# Clock_circuit.net
KiCad netlist of a schematic drawn in Altium Designer
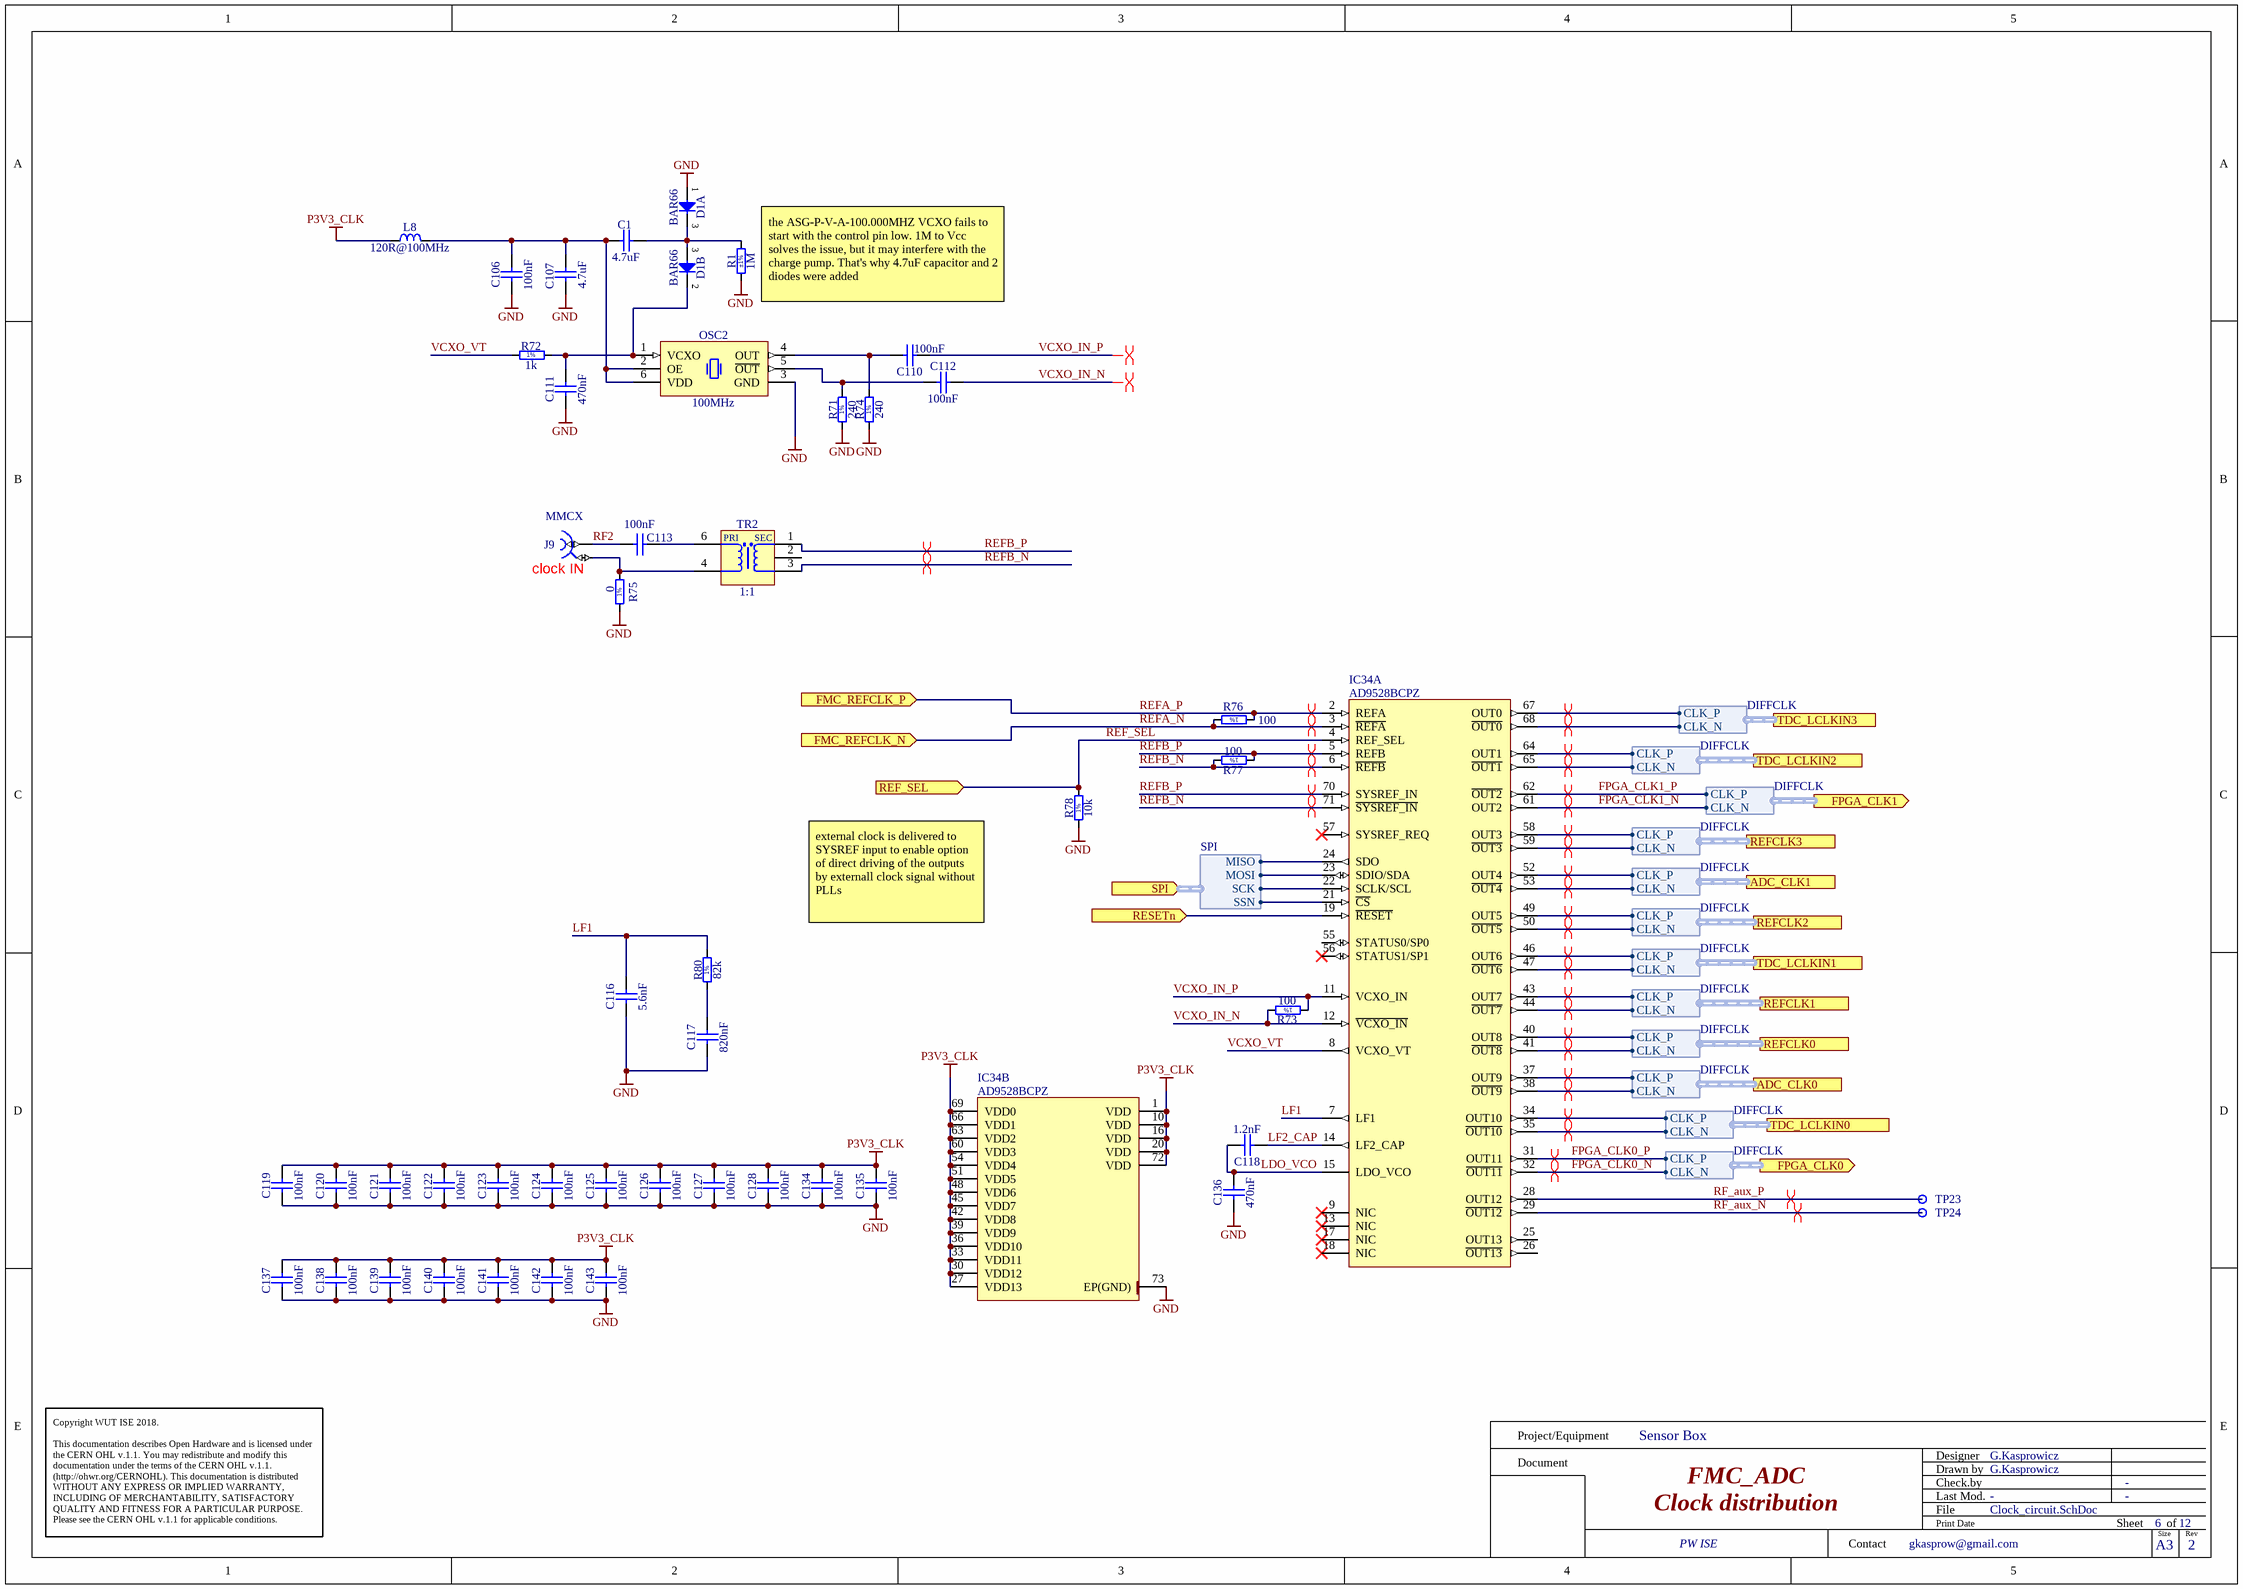
[diagram p0: Clock_circuit.SchDoc]

(export (version "E")
  (design (tool "Eeschema 10.0.6"))
  (components
    (comp (ref "C1")
      (value "4.7uF")
      (footprint "CAPC1608X87N")
      (description "Non-polarised capacitor")
      (fields
        (field (name "PART NUMBER") "CC0603_4.7UF_6.3V_10%_X5R")
        (field (name "VOLTAGE") "6.3V")
        (field (name "AUTHOR") "CERN DEM JLC")
      )
      (libsource (lib "Capacitors") (part "Capacitor - non polarized"))
    )
    (comp (ref "C106")
      (value "100nF")
      (footprint "CAPC0603X33N")
      (description "Non-polarised capacitor")
      (fields
        (field (name "TOLERANCE") "±10%")
        (field (name "PART NUMBER") "CC0201_100NF_6.3V_10%_X5R")
        (field (name "AUTHOR") "CERN DEM JLC")
      )
      (libsource (lib "Capacitors") (part "Capacitor - non polarized"))
    )
    (comp (ref "C107")
      (value "4.7uF")
      (footprint "CAPC1608X87N")
      (description "Non-polarised capacitor")
      (fields
        (field (name "PART NUMBER") "CC0603_4.7UF_6.3V_10%_X5R")
        (field (name "VOLTAGE") "6.3V")
        (field (name "AUTHOR") "CERN DEM JLC")
      )
      (libsource (lib "Capacitors") (part "Capacitor - non polarized"))
    )
    (comp (ref "C110")
      (value "100nF")
      (footprint "CAPC0603X33N")
      (description "Non-polarised capacitor")
      (fields
        (field (name "TOLERANCE") "±10%")
        (field (name "PART NUMBER") "CC0201_100NF_6.3V_10%_X5R")
        (field (name "AUTHOR") "CERN DEM JLC")
      )
      (libsource (lib "Capacitors") (part "Capacitor - non polarized"))
    )
    (comp (ref "C111")
      (value "470nF")
      (footprint "CAPC1005X55N")
      (description "Non-polarised capacitor")
      (fields
        (field (name "TOLERANCE") "±10%")
        (field (name "PART NUMBER") "CC0402_470NF_6.3V_10%_X5R")
        (field (name "AUTHOR") "CERN DEM JLC")
      )
      (libsource (lib "Capacitors") (part "Capacitor - non polarized"))
    )
    (comp (ref "C112")
      (value "100nF")
      (footprint "CAPC0603X33N")
      (description "Non-polarised capacitor")
      (fields
        (field (name "TOLERANCE") "±10%")
        (field (name "PART NUMBER") "CC0201_100NF_6.3V_10%_X5R")
        (field (name "AUTHOR") "CERN DEM JLC")
      )
      (libsource (lib "Capacitors") (part "Capacitor - non polarized"))
    )
    (comp (ref "C113")
      (value "100nF")
      (footprint "CAPC0603X33N")
      (description "Non-polarised capacitor")
      (fields
        (field (name "PART NUMBER") "CC0201_100NF_6.3V_10%_X5R")
        (field (name "VOLTAGE") "6.3V")
        (field (name "AUTHOR") "CERN DEM JLC")
      )
      (libsource (lib "Capacitors") (part "Capacitor - non polarized"))
    )
    (comp (ref "C116")
      (value "5.6nF")
      (footprint "CAPC2012X88N")
      (description "Non-polarised capacitor")
      (fields
        (field (name "PART NUMBER") "CC0805_5.6NF_50V_5%_C0G")
        (field (name "VOLTAGE") "50V")
        (field (name "AUTHOR") "*")
      )
      (libsource (lib "FMC_ADC") (part "CC0805_5.6NF_50V_5%_C0G"))
    )
    (comp (ref "C117")
      (value "820nF")
      (footprint "CAPC3216X130N")
      (description "Non-polarised capacitor")
      (fields (field (name "PART NUMBER") "CC1206_820NF_25V_10%_X7R") (field (name "VOLTAGE") "25V"))
      (libsource (lib "FMC_ADC") (part "CC1206_820NF_25V_10%_X7R"))
    )
    (comp (ref "C118")
      (value "1.2nF")
      (footprint "CAPC1608X80N")
      (description "Non-polarised capacitor")
      (fields
        (field (name "TOLERANCE") "±5%")
        (field (name "PART NUMBER") "CC0603_1.2NF_50V_5%_C0G")
        (field (name "AUTHOR") "*")
      )
      (libsource (lib "FMC_ADC") (part "CC0603_1.2NF_50V_5%_C0G"))
    )
    (comp (ref "C119")
      (value "100nF")
      (footprint "CAPC0603X33N")
      (description "Non-polarised capacitor")
      (fields
        (field (name "TOLERANCE") "±10%")
        (field (name "PART NUMBER") "CC0201_100NF_6.3V_10%_X5R")
        (field (name "AUTHOR") "CERN DEM JLC")
      )
      (libsource (lib "Capacitors") (part "Capacitor - non polarized"))
    )
    (comp (ref "C120")
      (value "100nF")
      (footprint "CAPC0603X33N")
      (description "Non-polarised capacitor")
      (fields
        (field (name "TOLERANCE") "±10%")
        (field (name "PART NUMBER") "CC0201_100NF_6.3V_10%_X5R")
        (field (name "AUTHOR") "CERN DEM JLC")
      )
      (libsource (lib "Capacitors") (part "Capacitor - non polarized"))
    )
    (comp (ref "C121")
      (value "100nF")
      (footprint "CAPC0603X33N")
      (description "Non-polarised capacitor")
      (fields
        (field (name "TOLERANCE") "±10%")
        (field (name "PART NUMBER") "CC0201_100NF_6.3V_10%_X5R")
        (field (name "AUTHOR") "CERN DEM JLC")
      )
      (libsource (lib "Capacitors") (part "Capacitor - non polarized"))
    )
    (comp (ref "C122")
      (value "100nF")
      (footprint "CAPC0603X33N")
      (description "Non-polarised capacitor")
      (fields
        (field (name "TOLERANCE") "±10%")
        (field (name "PART NUMBER") "CC0201_100NF_6.3V_10%_X5R")
        (field (name "AUTHOR") "CERN DEM JLC")
      )
      (libsource (lib "Capacitors") (part "Capacitor - non polarized"))
    )
    (comp (ref "C123")
      (value "100nF")
      (footprint "CAPC0603X33N")
      (description "Non-polarised capacitor")
      (fields
        (field (name "TOLERANCE") "±10%")
        (field (name "PART NUMBER") "CC0201_100NF_6.3V_10%_X5R")
        (field (name "AUTHOR") "CERN DEM JLC")
      )
      (libsource (lib "Capacitors") (part "Capacitor - non polarized"))
    )
    (comp (ref "C124")
      (value "100nF")
      (footprint "CAPC0603X33N")
      (description "Non-polarised capacitor")
      (fields
        (field (name "TOLERANCE") "±10%")
        (field (name "PART NUMBER") "CC0201_100NF_6.3V_10%_X5R")
        (field (name "AUTHOR") "CERN DEM JLC")
      )
      (libsource (lib "Capacitors") (part "Capacitor - non polarized"))
    )
    (comp (ref "C125")
      (value "100nF")
      (footprint "CAPC0603X33N")
      (description "Non-polarised capacitor")
      (fields
        (field (name "TOLERANCE") "±10%")
        (field (name "PART NUMBER") "CC0201_100NF_6.3V_10%_X5R")
        (field (name "AUTHOR") "CERN DEM JLC")
      )
      (libsource (lib "Capacitors") (part "Capacitor - non polarized"))
    )
    (comp (ref "C126")
      (value "100nF")
      (footprint "CAPC0603X33N")
      (description "Non-polarised capacitor")
      (fields
        (field (name "TOLERANCE") "±10%")
        (field (name "PART NUMBER") "CC0201_100NF_6.3V_10%_X5R")
        (field (name "AUTHOR") "CERN DEM JLC")
      )
      (libsource (lib "Capacitors") (part "Capacitor - non polarized"))
    )
    (comp (ref "C127")
      (value "100nF")
      (footprint "CAPC0603X33N")
      (description "Non-polarised capacitor")
      (fields
        (field (name "TOLERANCE") "±10%")
        (field (name "PART NUMBER") "CC0201_100NF_6.3V_10%_X5R")
        (field (name "AUTHOR") "CERN DEM JLC")
      )
      (libsource (lib "Capacitors") (part "Capacitor - non polarized"))
    )
    (comp (ref "C128")
      (value "100nF")
      (footprint "CAPC0603X33N")
      (description "Non-polarised capacitor")
      (fields
        (field (name "TOLERANCE") "±10%")
        (field (name "PART NUMBER") "CC0201_100NF_6.3V_10%_X5R")
        (field (name "AUTHOR") "CERN DEM JLC")
      )
      (libsource (lib "Capacitors") (part "Capacitor - non polarized"))
    )
    (comp (ref "C134")
      (value "100nF")
      (footprint "CAPC0603X33N")
      (description "Non-polarised capacitor")
      (fields
        (field (name "TOLERANCE") "±10%")
        (field (name "PART NUMBER") "CC0201_100NF_6.3V_10%_X5R")
        (field (name "AUTHOR") "CERN DEM JLC")
      )
      (libsource (lib "Capacitors") (part "Capacitor - non polarized"))
    )
    (comp (ref "C135")
      (value "100nF")
      (footprint "CAPC0603X33N")
      (description "Non-polarised capacitor")
      (fields
        (field (name "TOLERANCE") "±10%")
        (field (name "PART NUMBER") "CC0201_100NF_6.3V_10%_X5R")
        (field (name "AUTHOR") "CERN DEM JLC")
      )
      (libsource (lib "Capacitors") (part "Capacitor - non polarized"))
    )
    (comp (ref "C136")
      (value "470nF")
      (footprint "CAPC1005X55N")
      (description "Non-polarised capacitor")
      (fields
        (field (name "TOLERANCE") "±10%")
        (field (name "PART NUMBER") "CC0402_470NF_6.3V_10%_X5R")
        (field (name "AUTHOR") "CERN DEM JLC")
      )
      (libsource (lib "Capacitors") (part "Capacitor - non polarized"))
    )
    (comp (ref "C137")
      (value "100nF")
      (footprint "CAPC0603X33N")
      (description "Non-polarised capacitor")
      (fields
        (field (name "TOLERANCE") "±10%")
        (field (name "PART NUMBER") "CC0201_100NF_6.3V_10%_X5R")
        (field (name "AUTHOR") "CERN DEM JLC")
      )
      (libsource (lib "Capacitors") (part "Capacitor - non polarized"))
    )
    (comp (ref "C138")
      (value "100nF")
      (footprint "CAPC0603X33N")
      (description "Non-polarised capacitor")
      (fields
        (field (name "TOLERANCE") "±10%")
        (field (name "PART NUMBER") "CC0201_100NF_6.3V_10%_X5R")
        (field (name "AUTHOR") "CERN DEM JLC")
      )
      (libsource (lib "Capacitors") (part "Capacitor - non polarized"))
    )
    (comp (ref "C139")
      (value "100nF")
      (footprint "CAPC0603X33N")
      (description "Non-polarised capacitor")
      (fields
        (field (name "TOLERANCE") "±10%")
        (field (name "PART NUMBER") "CC0201_100NF_6.3V_10%_X5R")
        (field (name "AUTHOR") "CERN DEM JLC")
      )
      (libsource (lib "Capacitors") (part "Capacitor - non polarized"))
    )
    (comp (ref "C140")
      (value "100nF")
      (footprint "CAPC0603X33N")
      (description "Non-polarised capacitor")
      (fields
        (field (name "TOLERANCE") "±10%")
        (field (name "PART NUMBER") "CC0201_100NF_6.3V_10%_X5R")
        (field (name "AUTHOR") "CERN DEM JLC")
      )
      (libsource (lib "Capacitors") (part "Capacitor - non polarized"))
    )
    (comp (ref "C141")
      (value "100nF")
      (footprint "CAPC0603X33N")
      (description "Non-polarised capacitor")
      (fields
        (field (name "TOLERANCE") "±10%")
        (field (name "PART NUMBER") "CC0201_100NF_6.3V_10%_X5R")
        (field (name "AUTHOR") "CERN DEM JLC")
      )
      (libsource (lib "Capacitors") (part "Capacitor - non polarized"))
    )
    (comp (ref "C142")
      (value "100nF")
      (footprint "CAPC0603X33N")
      (description "Non-polarised capacitor")
      (fields
        (field (name "TOLERANCE") "±10%")
        (field (name "PART NUMBER") "CC0201_100NF_6.3V_10%_X5R")
        (field (name "AUTHOR") "CERN DEM JLC")
      )
      (libsource (lib "Capacitors") (part "Capacitor - non polarized"))
    )
    (comp (ref "C143")
      (value "100nF")
      (footprint "CAPC0603X33N")
      (description "Non-polarised capacitor")
      (fields
        (field (name "TOLERANCE") "±10%")
        (field (name "PART NUMBER") "CC0201_100NF_6.3V_10%_X5R")
        (field (name "AUTHOR") "CERN DEM JLC")
      )
      (libsource (lib "Capacitors") (part "Capacitor - non polarized"))
    )
    (comp (ref "D1")
      (value "BAR66")
      (footprint "SOT95P240X110-3N")
      (description "Serial Diode")
      (fields
        (field (name "VOLTAGE") "150V")
        (field (name "POWER") "250mA")
        (field (name "AUTHOR") "CERN DEM JLC")
      )
      (libsource (lib "ICs And Semiconductors") (part "Diode x2 A1C3_A3C2"))
    )
    (comp (ref "IC34")
      (value "AD9528BCPZ")
      (footprint "QFN50P1000X1000X100-73N-S545")
      (description "Clock Generator with 14 LVDS/HSTL Outputs")
      (fields (field (name "MANUFACTURER") "ANALOG DEVICES") (field (name "AUTHOR") "CERN DEM JLC"))
      (libsource (lib "ICs And Semiconductors") (part "AD9528"))
    )
    (comp (ref "J9")
      (value "Coax_1Female_1Shield")
      (footprint "HUBER-SUHNER_85_MMCX-50-0-1/111 OH")
      (fields
        (field (name "PART NUMBER") "HUBER-SUHNER_85_MMCX-50-0-1/111 OH")
        (field (name "FAMILY") "MMCX")
        (field (name "MANUFACTURER") "HUBER+SUHNER")
        (field (name "MANUFACTURER PART NUMBER") "85_MMCX-50-0-1/111 OH")
        (field (name "AUTHOR") "CERN DEM JLC")
      )
      (libsource (lib "Connectors") (part "Coax_1Female_1Shield"))
    )
    (comp (ref "L8")
      (value "120R@100MHz")
      (footprint "INDC1608X65N")
      (description "Inductor")
      (fields
        (field (name "PART NUMBER") "IND0603_MURATA_BLM18SG121TN1D")
        (field (name "POWER") "3A")
        (field (name "AUTHOR") "CERN DEM JLC")
      )
      (libsource (lib "Inductors & Transformers") (part "Inductor"))
    )
    (comp (ref "OSC2")
      (value "100MHz")
      (footprint "OSCSC254P500X700X190-6N")
      (description "VCXO 100MHz Oscillator")
      (fields
        (field (name "PART NUMBER") "OSC_100MHZ_ABRACON_ASG-P-V-A-100.000MHZ")
        (field (name "MANUFACTURER") "ABRACON")
        (field (name "AUTHOR") "GK")
      )
      (libsource (lib "LIBRARY_SCH") (part "OSC_100MHz_LVPECL"))
    )
    (comp (ref "R1")
      (value "1M")
      (footprint "RESC1005X40N")
      (description "Resistor - 1%")
      (fields
        (field (name "TOLERANCE") "±1%")
        (field (name "PART NUMBER") "R0402_1M_1%_0.0625W_100PPM")
        (field (name "POWER") "0.0625W")
        (field (name "AUTHOR") "CERN DEM JLC")
      )
      (libsource (lib "Resistors") (part "Resistor - 1%"))
    )
    (comp (ref "R71")
      (value "240")
      (footprint "RESC1005X40N")
      (description "Resistor - 1%")
      (fields
        (field (name "PART NUMBER") "R0402_240R_1%_0.0625W_100PPM")
        (field (name "POWER") "0.0625W")
        (field (name "AUTHOR") "CERN DEM JLC")
      )
      (libsource (lib "Resistors") (part "Resistor - 1%"))
    )
    (comp (ref "R72")
      (value "1k")
      (footprint "RESC1005X40N")
      (description "Resistor - 1%")
      (fields
        (field (name "TOLERANCE") "±1%")
        (field (name "POWER") "0.0625W")
        (field (name "AUTHOR") "CERN DEM JLC")
      )
      (libsource (lib "Resistors") (part "Resistor - 1%"))
    )
    (comp (ref "R73")
      (value "100")
      (footprint "RESC0603X28N")
      (description "Resistor - 1%")
      (fields
        (field (name "PART NUMBER") "R0201_100R_1%_0.05W_200PPM")
        (field (name "POWER") "0.05W")
        (field (name "AUTHOR") "CERN DEM JLC")
      )
      (libsource (lib "Resistors") (part "Resistor - 1%"))
    )
    (comp (ref "R74")
      (value "240")
      (footprint "RESC1005X40N")
      (description "Resistor - 1%")
      (fields
        (field (name "PART NUMBER") "R0402_240R_1%_0.0625W_100PPM")
        (field (name "POWER") "0.0625W")
        (field (name "AUTHOR") "CERN DEM JLC")
      )
      (libsource (lib "Resistors") (part "Resistor - 1%"))
    )
    (comp (ref "R75")
      (value "0")
      (footprint "RESC1005X40N")
      (description "Resistor - 1%")
      (fields
        (field (name "PART NUMBER") "R0402_0R_JUMPER")
        (field (name "MANUFACTURER") "GENERIC")
        (field (name "AUTHOR") "CERN DEM JLC")
      )
      (libsource (lib "Resistors") (part "Resistor - 1%"))
    )
    (comp (ref "R76")
      (value "100")
      (footprint "RESC0603X28N")
      (description "Resistor - 1%")
      (fields
        (field (name "PART NUMBER") "R0201_100R_1%_0.05W_200PPM")
        (field (name "POWER") "0.05W")
        (field (name "AUTHOR") "CERN DEM JLC")
      )
      (libsource (lib "Resistors") (part "Resistor - 1%"))
    )
    (comp (ref "R77")
      (value "100")
      (footprint "RESC0603X28N")
      (description "Resistor - 1%")
      (fields
        (field (name "PART NUMBER") "R0201_100R_1%_0.05W_200PPM")
        (field (name "POWER") "0.05W")
        (field (name "AUTHOR") "CERN DEM JLC")
      )
      (libsource (lib "Resistors") (part "Resistor - 1%"))
    )
    (comp (ref "R78")
      (value "10k")
      (footprint "RESC1005X40N")
      (description "Resistor - 1%")
      (fields
        (field (name "PART NUMBER") "R0402_10K_1%_0.0625W_100PPM")
        (field (name "POWER") "0.0625W")
        (field (name "AUTHOR") "CERN DEM JLC")
      )
      (libsource (lib "Resistors") (part "Resistor - 1%"))
    )
    (comp (ref "R80")
      (value "82k")
      (footprint "RESC1005X40N")
      (description "Resistor - 1%")
      (fields
        (field (name "TOLERANCE") "±1%")
        (field (name "POWER") "0.0625W")
        (field (name "AUTHOR") "CERN DEM JLC")
      )
      (libsource (lib "Resistors") (part "Resistor - 1%"))
    )
    (comp (ref "TP23")
      (value "Test Point")
      (footprint "TPS127")
      (fields (field (name "PART NUMBER") "SMD_PAD_1.27X1.27MM") (field (name "AUTHOR") "CERN DEM JLC"))
      (libsource (lib "Eletro-mechanical") (part "Test Point"))
    )
    (comp (ref "TP24")
      (value "Test Point")
      (footprint "TPS127")
      (fields (field (name "PART NUMBER") "SMD_PAD_1.27X1.27MM") (field (name "AUTHOR") "CERN DEM JLC"))
      (libsource (lib "Eletro-mechanical") (part "Test Point"))
    )
    (comp (ref "TR2")
      (value "1:1")
      (footprint "XFMR_MINI-CIRCUITS_AT224-1")
      (description "50 Ohm  0.4 To 500MHz RF Transformers")
      (fields
        (field (name "PART NUMBER") "XFMR_MINI-CIRCUITS_TC1-1T+")
        (field (name "MANUFACTURER") "MINI-CIRCUITS")
        (field (name "AUTHOR") "CERN DEM JLC")
      )
      (libsource (lib "Inductors & Transformers") (part "XFMR_MINI-CIRCUITS_TC1-1+"))
    )
  )
  (nets
    (net (code "3") (name "/FPGA_CLK0_N") (class "Default")
      (node (ref "IC34") (pin "32") (pinfunction "~{OUT11}_32") (pintype "output"))
    )
    (net (code "4") (name "/FPGA_CLK0_P") (class "Default")
      (node (ref "IC34") (pin "31") (pinfunction "OUT11_31") (pintype "output"))
    )
    (net (code "5") (name "/FPGA_CLK1_N") (class "Default")
      (node (ref "IC34") (pin "61") (pinfunction "OUT2_61") (pintype "output"))
    )
    (net (code "6") (name "/FPGA_CLK1_P") (class "Default")
      (node (ref "IC34") (pin "62") (pinfunction "~{OUT2}_62") (pintype "output"))
    )
    (net (code "7") (name "/LDO_VCO") (class "Default")
      (node (ref "C118") (pin "2") (pinfunction "2_2") (pintype "passive"))
      (node (ref "C136") (pin "2") (pinfunction "2_2") (pintype "passive"))
      (node (ref "IC34") (pin "15") (pinfunction "LDO_VCO_15") (pintype "power_in"))
    )
    (net (code "8") (name "/LF1") (class "Default")
      (node (ref "C116") (pin "2") (pinfunction "2_2") (pintype "passive"))
      (node (ref "IC34") (pin "7") (pinfunction "LF1_7") (pintype "output"))
      (node (ref "R80") (pin "2") (pinfunction "2_2") (pintype "passive"))
    )
    (net (code "9") (name "/LF2_CAP") (class "Default")
      (node (ref "C118") (pin "1") (pinfunction "1_1") (pintype "passive"))
      (node (ref "IC34") (pin "14") (pinfunction "LF2_CAP_14") (pintype "output"))
    )
    (net (code "10") (name "/MISO") (class "Default")
      (node (ref "IC34") (pin "24") (pinfunction "SDO_24") (pintype "output"))
    )
    (net (code "11") (name "/MOSI") (class "Default")
      (node (ref "IC34") (pin "23") (pinfunction "SDIO/SDA_23") (pintype "bidirectional"))
    )
    (net (code "12") (name "/REFA_N") (class "Default")
      (node (ref "IC34") (pin "3") (pinfunction "~{REFA}_3") (pintype "input"))
      (node (ref "R76") (pin "2") (pinfunction "2_2") (pintype "passive"))
    )
    (net (code "13") (name "/REFA_P") (class "Default")
      (node (ref "IC34") (pin "2") (pinfunction "REFA_2") (pintype "input"))
      (node (ref "R76") (pin "1") (pinfunction "1_1") (pintype "passive"))
    )
    (net (code "14") (name "/REFB_N") (class "Default")
      (node (ref "IC34") (pin "6") (pinfunction "~{REFB}_6") (pintype "input"))
      (node (ref "IC34") (pin "71") (pinfunction "~{SYSREF_IN}_71") (pintype "input"))
      (node (ref "R77") (pin "2") (pinfunction "2_2") (pintype "passive"))
      (node (ref "TR2") (pin "3") (pinfunction "S_3") (pintype "passive"))
    )
    (net (code "15") (name "/REFB_P") (class "Default")
      (node (ref "IC34") (pin "5") (pinfunction "REFB_5") (pintype "input"))
      (node (ref "IC34") (pin "70") (pinfunction "SYSREF_IN_70") (pintype "input"))
      (node (ref "R77") (pin "1") (pinfunction "1_1") (pintype "passive"))
      (node (ref "TR2") (pin "1") (pinfunction "SDOT_1") (pintype "passive"))
    )
    (net (code "16") (name "/REF_SEL") (class "Default")
      (node (ref "IC34") (pin "4") (pinfunction "REF_SEL_4") (pintype "input"))
      (node (ref "R78") (pin "2") (pinfunction "2_2") (pintype "passive"))
    )
    (net (code "17") (name "/RESETn") (class "Default")
      (node (ref "IC34") (pin "19") (pinfunction "~{RESET}_19") (pintype "input"))
    )
    (net (code "18") (name "/RF2") (class "Default")
      (node (ref "C113") (pin "2") (pinfunction "2_2") (pintype "passive"))
      (node (ref "J9") (pin "1") (pinfunction "1_1") (pintype "bidirectional"))
    )
    (net (code "19") (name "/RF_aux_N") (class "Default")
      (node (ref "IC34") (pin "29") (pinfunction "~{OUT12}_29") (pintype "output"))
      (node (ref "TP24") (pin "1") (pinfunction "1_1") (pintype "bidirectional"))
    )
    (net (code "20") (name "/RF_aux_P") (class "Default")
      (node (ref "IC34") (pin "28") (pinfunction "OUT12_28") (pintype "output"))
      (node (ref "TP23") (pin "1") (pinfunction "1_1") (pintype "bidirectional"))
    )
    (net (code "21") (name "/SCK") (class "Default")
      (node (ref "IC34") (pin "22") (pinfunction "SCLK/SCL_22") (pintype "input"))
    )
    (net (code "22") (name "/SSN") (class "Default")
      (node (ref "IC34") (pin "21") (pinfunction "~{CS}_21") (pintype "input"))
    )
    (net (code "23") (name "/VCXO_IN_N") (class "Default")
      (node (ref "C112") (pin "2") (pinfunction "2_2") (pintype "passive"))
      (node (ref "IC34") (pin "12") (pinfunction "~{VCXO_IN}_12") (pintype "input"))
      (node (ref "R73") (pin "2") (pinfunction "2_2") (pintype "passive"))
    )
    (net (code "24") (name "/VCXO_IN_P") (class "Default")
      (node (ref "C110") (pin "1") (pinfunction "1_1") (pintype "passive"))
      (node (ref "IC34") (pin "11") (pinfunction "VCXO_IN_11") (pintype "input"))
      (node (ref "R73") (pin "1") (pinfunction "1_1") (pintype "passive"))
    )
    (net (code "25") (name "/VCXO_VT") (class "Default")
      (node (ref "IC34") (pin "8") (pinfunction "VCXO_VT_8") (pintype "output"))
      (node (ref "R72") (pin "1") (pinfunction "1_1") (pintype "passive"))
    )
    (net (code "28") (name "GND") (class "Default")
      (node (ref "C106") (pin "1") (pinfunction "1_1") (pintype "passive"))
      (node (ref "C107") (pin "1") (pinfunction "1_1") (pintype "passive"))
      (node (ref "C111") (pin "1") (pinfunction "1_1") (pintype "passive"))
      (node (ref "C116") (pin "1") (pinfunction "1_1") (pintype "passive"))
      (node (ref "C117") (pin "1") (pinfunction "1_1") (pintype "passive"))
      (node (ref "C119") (pin "1") (pinfunction "1_1") (pintype "passive"))
      (node (ref "C120") (pin "1") (pinfunction "1_1") (pintype "passive"))
      (node (ref "C121") (pin "1") (pinfunction "1_1") (pintype "passive"))
      (node (ref "C122") (pin "1") (pinfunction "1_1") (pintype "passive"))
      (node (ref "C123") (pin "1") (pinfunction "1_1") (pintype "passive"))
      (node (ref "C124") (pin "1") (pinfunction "1_1") (pintype "passive"))
      (node (ref "C125") (pin "1") (pinfunction "1_1") (pintype "passive"))
      (node (ref "C126") (pin "1") (pinfunction "1_1") (pintype "passive"))
      (node (ref "C127") (pin "1") (pinfunction "1_1") (pintype "passive"))
      (node (ref "C128") (pin "1") (pinfunction "1_1") (pintype "passive"))
      (node (ref "C134") (pin "1") (pinfunction "1_1") (pintype "passive"))
      (node (ref "C135") (pin "1") (pinfunction "1_1") (pintype "passive"))
      (node (ref "C136") (pin "1") (pinfunction "1_1") (pintype "passive"))
      (node (ref "C137") (pin "1") (pinfunction "1_1") (pintype "passive"))
      (node (ref "C138") (pin "1") (pinfunction "1_1") (pintype "passive"))
      (node (ref "C139") (pin "1") (pinfunction "1_1") (pintype "passive"))
      (node (ref "C140") (pin "1") (pinfunction "1_1") (pintype "passive"))
      (node (ref "C141") (pin "1") (pinfunction "1_1") (pintype "passive"))
      (node (ref "C142") (pin "1") (pinfunction "1_1") (pintype "passive"))
      (node (ref "C143") (pin "1") (pinfunction "1_1") (pintype "passive"))
      (node (ref "D1") (pin "1") (pinfunction "A_1") (pintype "passive"))
      (node (ref "IC34") (pin "73") (pinfunction "EP(GND)_73") (pintype "power_in"))
      (node (ref "OSC2") (pin "3") (pinfunction "GND_3") (pintype "power_in"))
      (node (ref "R1") (pin "1") (pinfunction "1_1") (pintype "passive"))
      (node (ref "R71") (pin "1") (pinfunction "1_1") (pintype "passive"))
      (node (ref "R74") (pin "1") (pinfunction "1_1") (pintype "passive"))
      (node (ref "R75") (pin "1") (pinfunction "1_1") (pintype "passive"))
      (node (ref "R78") (pin "1") (pinfunction "1_1") (pintype "passive"))
    )
    (net (code "29") (name "Net-(C117-Pad2)") (class "Default")
      (node (ref "C117") (pin "2") (pinfunction "2_2") (pintype "passive"))
      (node (ref "R80") (pin "1") (pinfunction "1_1") (pintype "passive"))
    )
    (net (code "30") (name "Net-(D1A-COMAC)") (class "Default")
      (node (ref "C1") (pin "2") (pinfunction "2_2") (pintype "passive"))
      (node (ref "D1") (pin "3") (pinfunction "COMAC_3") (pintype "passive"))
      (node (ref "R1") (pin "2") (pinfunction "2_2") (pintype "passive"))
    )
    (net (code "31") (name "Net-(D1B-C)") (class "Default")
      (node (ref "C111") (pin "2") (pinfunction "2_2") (pintype "passive"))
      (node (ref "D1") (pin "2") (pinfunction "C_2") (pintype "passive"))
      (node (ref "OSC2") (pin "1") (pinfunction "VCXO_1") (pintype "input"))
      (node (ref "R72") (pin "2") (pinfunction "2_2") (pintype "passive"))
    )
    (net (code "32") (name "Net-(OSC2-OE)") (class "Default")
      (node (ref "C1") (pin "1") (pinfunction "1_1") (pintype "passive"))
      (node (ref "C106") (pin "2") (pinfunction "2_2") (pintype "passive"))
      (node (ref "C107") (pin "2") (pinfunction "2_2") (pintype "passive"))
      (node (ref "L8") (pin "2") (pinfunction "2_2") (pintype "passive"))
      (node (ref "OSC2") (pin "2") (pinfunction "OE_2") (pintype "passive"))
      (node (ref "OSC2") (pin "6") (pinfunction "VDD_6") (pintype "power_in"))
    )
    (net (code "33") (name "Net-(OSC2-OUT)") (class "Default")
      (node (ref "C110") (pin "2") (pinfunction "2_2") (pintype "passive"))
      (node (ref "OSC2") (pin "4") (pinfunction "OUT_4") (pintype "output"))
      (node (ref "R74") (pin "2") (pinfunction "2_2") (pintype "passive"))
    )
    (net (code "34") (name "Net-(OSC2-~{OUT})") (class "Default")
      (node (ref "C112") (pin "1") (pinfunction "1_1") (pintype "passive"))
      (node (ref "OSC2") (pin "5") (pinfunction "~{OUT}_5") (pintype "output"))
      (node (ref "R71") (pin "2") (pinfunction "2_2") (pintype "passive"))
    )
    (net (code "35") (name "Net-(TR2-P)") (class "Default")
      (node (ref "J9") (pin "2") (pinfunction "2_2") (pintype "bidirectional"))
      (node (ref "R75") (pin "2") (pinfunction "2_2") (pintype "passive"))
      (node (ref "TR2") (pin "4") (pinfunction "P_4") (pintype "passive"))
    )
    (net (code "36") (name "Net-(TR2-PDOT)") (class "Default")
      (node (ref "C113") (pin "1") (pinfunction "1_1") (pintype "passive"))
      (node (ref "TR2") (pin "6") (pinfunction "PDOT_6") (pintype "passive"))
    )
    (net (code "37") (name "P3V3_CLK") (class "Default")
      (node (ref "C119") (pin "2") (pinfunction "2_2") (pintype "passive"))
      (node (ref "C120") (pin "2") (pinfunction "2_2") (pintype "passive"))
      (node (ref "C121") (pin "2") (pinfunction "2_2") (pintype "passive"))
      (node (ref "C122") (pin "2") (pinfunction "2_2") (pintype "passive"))
      (node (ref "C123") (pin "2") (pinfunction "2_2") (pintype "passive"))
      (node (ref "C124") (pin "2") (pinfunction "2_2") (pintype "passive"))
      (node (ref "C125") (pin "2") (pinfunction "2_2") (pintype "passive"))
      (node (ref "C126") (pin "2") (pinfunction "2_2") (pintype "passive"))
      (node (ref "C127") (pin "2") (pinfunction "2_2") (pintype "passive"))
      (node (ref "C128") (pin "2") (pinfunction "2_2") (pintype "passive"))
      (node (ref "C134") (pin "2") (pinfunction "2_2") (pintype "passive"))
      (node (ref "C135") (pin "2") (pinfunction "2_2") (pintype "passive"))
      (node (ref "C137") (pin "2") (pinfunction "2_2") (pintype "passive"))
      (node (ref "C138") (pin "2") (pinfunction "2_2") (pintype "passive"))
      (node (ref "C139") (pin "2") (pinfunction "2_2") (pintype "passive"))
      (node (ref "C140") (pin "2") (pinfunction "2_2") (pintype "passive"))
      (node (ref "C141") (pin "2") (pinfunction "2_2") (pintype "passive"))
      (node (ref "C142") (pin "2") (pinfunction "2_2") (pintype "passive"))
      (node (ref "C143") (pin "2") (pinfunction "2_2") (pintype "passive"))
      (node (ref "IC34") (pin "1") (pinfunction "VDD_1") (pintype "power_in"))
      (node (ref "IC34") (pin "10") (pinfunction "VDD_10") (pintype "power_in"))
      (node (ref "IC34") (pin "16") (pinfunction "VDD_16") (pintype "power_in"))
      (node (ref "IC34") (pin "20") (pinfunction "VDD_20") (pintype "power_in"))
      (node (ref "IC34") (pin "27") (pinfunction "VDD13_27") (pintype "power_in"))
      (node (ref "IC34") (pin "30") (pinfunction "VDD12_30") (pintype "power_in"))
      (node (ref "IC34") (pin "33") (pinfunction "VDD11_33") (pintype "power_in"))
      (node (ref "IC34") (pin "36") (pinfunction "VDD10_36") (pintype "power_in"))
      (node (ref "IC34") (pin "39") (pinfunction "VDD9_39") (pintype "power_in"))
      (node (ref "IC34") (pin "42") (pinfunction "VDD8_42") (pintype "power_in"))
      (node (ref "IC34") (pin "45") (pinfunction "VDD7_45") (pintype "power_in"))
      (node (ref "IC34") (pin "48") (pinfunction "VDD6_48") (pintype "power_in"))
      (node (ref "IC34") (pin "51") (pinfunction "VDD5_51") (pintype "power_in"))
      (node (ref "IC34") (pin "54") (pinfunction "VDD4_54") (pintype "power_in"))
      (node (ref "IC34") (pin "60") (pinfunction "VDD3_60") (pintype "power_in"))
      (node (ref "IC34") (pin "63") (pinfunction "VDD2_63") (pintype "power_in"))
      (node (ref "IC34") (pin "66") (pinfunction "VDD1_66") (pintype "power_in"))
      (node (ref "IC34") (pin "69") (pinfunction "VDD0_69") (pintype "power_in"))
      (node (ref "IC34") (pin "72") (pinfunction "VDD_72") (pintype "power_in"))
      (node (ref "L8") (pin "1") (pinfunction "1_1") (pintype "passive"))
    )
    (net (code "38") (name "unconnected-(IC34A-NIC-Pad9)") (class "Default")
      (node (ref "IC34") (pin "9") (pinfunction "NIC_9") (pintype "passive+no_connect"))
    )
    (net (code "39") (name "unconnected-(IC34A-NIC-Pad13)") (class "Default")
      (node (ref "IC34") (pin "13") (pinfunction "NIC_13") (pintype "passive+no_connect"))
    )
    (net (code "40") (name "unconnected-(IC34A-NIC-Pad17)") (class "Default")
      (node (ref "IC34") (pin "17") (pinfunction "NIC_17") (pintype "passive+no_connect"))
    )
    (net (code "41") (name "unconnected-(IC34A-NIC-Pad18)") (class "Default")
      (node (ref "IC34") (pin "18") (pinfunction "NIC_18") (pintype "passive+no_connect"))
    )
    (net (code "42") (name "unconnected-(IC34A-OUT0-Pad67)") (class "Default")
      (node (ref "IC34") (pin "67") (pinfunction "OUT0_67") (pintype "output"))
    )
    (net (code "43") (name "unconnected-(IC34A-OUT1-Pad64)") (class "Default")
      (node (ref "IC34") (pin "64") (pinfunction "OUT1_64") (pintype "output"))
    )
    (net (code "44") (name "unconnected-(IC34A-OUT3-Pad58)") (class "Default")
      (node (ref "IC34") (pin "58") (pinfunction "OUT3_58") (pintype "output"))
    )
    (net (code "45") (name "unconnected-(IC34A-OUT4-Pad52)") (class "Default")
      (node (ref "IC34") (pin "52") (pinfunction "OUT4_52") (pintype "output"))
    )
    (net (code "46") (name "unconnected-(IC34A-OUT5-Pad49)") (class "Default")
      (node (ref "IC34") (pin "49") (pinfunction "OUT5_49") (pintype "output"))
    )
    (net (code "47") (name "unconnected-(IC34A-OUT6-Pad46)") (class "Default")
      (node (ref "IC34") (pin "46") (pinfunction "OUT6_46") (pintype "output"))
    )
    (net (code "48") (name "unconnected-(IC34A-OUT7-Pad43)") (class "Default")
      (node (ref "IC34") (pin "43") (pinfunction "OUT7_43") (pintype "output"))
    )
    (net (code "49") (name "unconnected-(IC34A-OUT8-Pad40)") (class "Default")
      (node (ref "IC34") (pin "40") (pinfunction "OUT8_40") (pintype "output"))
    )
    (net (code "50") (name "unconnected-(IC34A-OUT9-Pad37)") (class "Default")
      (node (ref "IC34") (pin "37") (pinfunction "OUT9_37") (pintype "output"))
    )
    (net (code "51") (name "unconnected-(IC34A-OUT10-Pad34)") (class "Default")
      (node (ref "IC34") (pin "34") (pinfunction "OUT10_34") (pintype "output"))
    )
    (net (code "52") (name "unconnected-(IC34A-OUT13-Pad25)") (class "Default")
      (node (ref "IC34") (pin "25") (pinfunction "OUT13_25") (pintype "output"))
    )
    (net (code "53") (name "unconnected-(IC34A-STATUS0{slash}SP0-Pad55)") (class "Default")
      (node (ref "IC34") (pin "55") (pinfunction "STATUS0/SP0_55") (pintype "bidirectional"))
    )
    (net (code "54") (name "unconnected-(IC34A-STATUS1{slash}SP1-Pad56)") (class "Default")
      (node (ref "IC34") (pin "56") (pinfunction "STATUS1/SP1_56") (pintype "bidirectional+no_connect"))
    )
    (net (code "55") (name "unconnected-(IC34A-SYSREF_REQ-Pad57)") (class "Default")
      (node (ref "IC34") (pin "57") (pinfunction "SYSREF_REQ_57") (pintype "input+no_connect"))
    )
    (net (code "56") (name "unconnected-(IC34A-~{OUT0}-Pad68)") (class "Default")
      (node (ref "IC34") (pin "68") (pinfunction "~{OUT0}_68") (pintype "output"))
    )
    (net (code "57") (name "unconnected-(IC34A-~{OUT1}-Pad65)") (class "Default")
      (node (ref "IC34") (pin "65") (pinfunction "~{OUT1}_65") (pintype "output"))
    )
    (net (code "58") (name "unconnected-(IC34A-~{OUT3}-Pad59)") (class "Default")
      (node (ref "IC34") (pin "59") (pinfunction "~{OUT3}_59") (pintype "output"))
    )
    (net (code "59") (name "unconnected-(IC34A-~{OUT4}-Pad53)") (class "Default")
      (node (ref "IC34") (pin "53") (pinfunction "~{OUT4}_53") (pintype "output"))
    )
    (net (code "60") (name "unconnected-(IC34A-~{OUT5}-Pad50)") (class "Default")
      (node (ref "IC34") (pin "50") (pinfunction "~{OUT5}_50") (pintype "output"))
    )
    (net (code "61") (name "unconnected-(IC34A-~{OUT6}-Pad47)") (class "Default")
      (node (ref "IC34") (pin "47") (pinfunction "~{OUT6}_47") (pintype "output"))
    )
    (net (code "62") (name "unconnected-(IC34A-~{OUT7}-Pad44)") (class "Default")
      (node (ref "IC34") (pin "44") (pinfunction "~{OUT7}_44") (pintype "output"))
    )
    (net (code "63") (name "unconnected-(IC34A-~{OUT8}-Pad41)") (class "Default")
      (node (ref "IC34") (pin "41") (pinfunction "~{OUT8}_41") (pintype "output"))
    )
    (net (code "64") (name "unconnected-(IC34A-~{OUT9}-Pad38)") (class "Default")
      (node (ref "IC34") (pin "38") (pinfunction "~{OUT9}_38") (pintype "output"))
    )
    (net (code "65") (name "unconnected-(IC34A-~{OUT10}-Pad35)") (class "Default")
      (node (ref "IC34") (pin "35") (pinfunction "~{OUT10}_35") (pintype "output"))
    )
    (net (code "66") (name "unconnected-(IC34A-~{OUT13}-Pad26)") (class "Default")
      (node (ref "IC34") (pin "26") (pinfunction "~{OUT13}_26") (pintype "output"))
    )
    (net (code "67") (name "unconnected-(TR2-NU-Pad2)") (class "Default")
      (node (ref "TR2") (pin "2") (pinfunction "NU_2") (pintype "passive"))
    )
  )
)
